# pentatonic.net
KiCad netlist of a schematic drawn in EAGLE
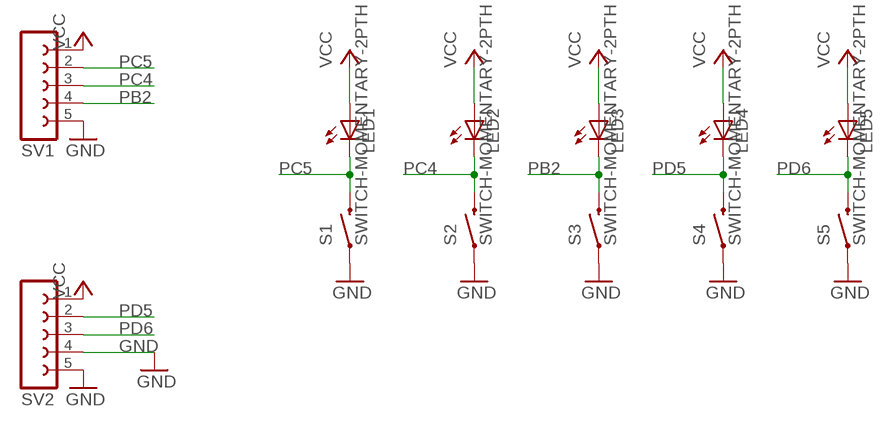
[diagram p0: schematic, sheet 1]

(export (version "E")
  (design (tool "Eeschema 10.0.6"))
  (components
    (comp (ref "LED1")
      (value "LED5MM")
      (footprint "eagle-import:LED5MM")
      (libsource (lib "eagle-import") (part "LED5MM"))
    )
    (comp (ref "LED2")
      (value "LED5MM")
      (footprint "eagle-import:LED5MM")
      (libsource (lib "eagle-import") (part "LED5MM"))
    )
    (comp (ref "LED3")
      (value "LED5MM")
      (footprint "eagle-import:LED5MM")
      (libsource (lib "eagle-import") (part "LED5MM"))
    )
    (comp (ref "LED4")
      (value "LED5MM")
      (footprint "eagle-import:LED5MM")
      (libsource (lib "eagle-import") (part "LED5MM"))
    )
    (comp (ref "LED5")
      (value "LED5MM")
      (footprint "eagle-import:LED5MM")
      (libsource (lib "eagle-import") (part "LED5MM"))
    )
    (comp (ref "S1")
      (value "SWITCH-MOMENTARY-2PTH")
      (footprint "eagle-import:TACTILE-PTH")
      (libsource (lib "eagle-import") (part "SWITCH-MOMENTARY-2PTH"))
    )
    (comp (ref "S2")
      (value "SWITCH-MOMENTARY-2PTH")
      (footprint "eagle-import:TACTILE-PTH")
      (libsource (lib "eagle-import") (part "SWITCH-MOMENTARY-2PTH"))
    )
    (comp (ref "S3")
      (value "SWITCH-MOMENTARY-2PTH")
      (footprint "eagle-import:TACTILE-PTH")
      (libsource (lib "eagle-import") (part "SWITCH-MOMENTARY-2PTH"))
    )
    (comp (ref "S4")
      (value "SWITCH-MOMENTARY-2PTH")
      (footprint "eagle-import:TACTILE-PTH")
      (libsource (lib "eagle-import") (part "SWITCH-MOMENTARY-2PTH"))
    )
    (comp (ref "S5")
      (value "SWITCH-MOMENTARY-2PTH")
      (footprint "eagle-import:TACTILE-PTH")
      (libsource (lib "eagle-import") (part "SWITCH-MOMENTARY-2PTH"))
    )
    (comp (ref "SV1")
      (value "FE05-1")
      (footprint "eagle-import:FE05-1")
      (libsource (lib "eagle-import") (part "FE05-1"))
    )
    (comp (ref "SV2")
      (value "FE05-1")
      (footprint "eagle-import:FE05-1")
      (libsource (lib "eagle-import") (part "FE05-1"))
    )
  )
  (nets
    (net (code "1") (name "/PB2") (class "Default")
      (node (ref "LED3") (pin "K") (pinfunction "C_K") (pintype "passive"))
      (node (ref "S3") (pin "3") (pinfunction "2_3") (pintype "passive"))
      (node (ref "SV1") (pin "4") (pinfunction "4_4") (pintype "passive"))
    )
    (net (code "2") (name "/PC4") (class "Default")
      (node (ref "LED2") (pin "K") (pinfunction "C_K") (pintype "passive"))
      (node (ref "S2") (pin "3") (pinfunction "2_3") (pintype "passive"))
      (node (ref "SV1") (pin "3") (pinfunction "3_3") (pintype "passive"))
    )
    (net (code "3") (name "/PC5") (class "Default")
      (node (ref "LED1") (pin "K") (pinfunction "C_K") (pintype "passive"))
      (node (ref "S1") (pin "3") (pinfunction "2_3") (pintype "passive"))
      (node (ref "SV1") (pin "2") (pinfunction "2_2") (pintype "passive"))
    )
    (net (code "4") (name "/PD5") (class "Default")
      (node (ref "LED4") (pin "K") (pinfunction "C_K") (pintype "passive"))
      (node (ref "S4") (pin "3") (pinfunction "2_3") (pintype "passive"))
      (node (ref "SV2") (pin "2") (pinfunction "2_2") (pintype "passive"))
    )
    (net (code "5") (name "/PD6") (class "Default")
      (node (ref "LED5") (pin "K") (pinfunction "C_K") (pintype "passive"))
      (node (ref "S5") (pin "3") (pinfunction "2_3") (pintype "passive"))
      (node (ref "SV2") (pin "3") (pinfunction "3_3") (pintype "passive"))
    )
    (net (code "6") (name "GND") (class "Default")
      (node (ref "S1") (pin "1") (pinfunction "1_1") (pintype "passive"))
      (node (ref "S2") (pin "1") (pinfunction "1_1") (pintype "passive"))
      (node (ref "S3") (pin "1") (pinfunction "1_1") (pintype "passive"))
      (node (ref "S4") (pin "1") (pinfunction "1_1") (pintype "passive"))
      (node (ref "S5") (pin "1") (pinfunction "1_1") (pintype "passive"))
      (node (ref "SV1") (pin "5") (pinfunction "5_5") (pintype "passive"))
      (node (ref "SV2") (pin "4") (pinfunction "4_4") (pintype "passive"))
      (node (ref "SV2") (pin "5") (pinfunction "5_5") (pintype "passive"))
    )
    (net (code "7") (name "VCC") (class "Default")
      (node (ref "LED1") (pin "A") (pinfunction "A_A") (pintype "passive"))
      (node (ref "LED2") (pin "A") (pinfunction "A_A") (pintype "passive"))
      (node (ref "LED3") (pin "A") (pinfunction "A_A") (pintype "passive"))
      (node (ref "LED4") (pin "A") (pinfunction "A_A") (pintype "passive"))
      (node (ref "LED5") (pin "A") (pinfunction "A_A") (pintype "passive"))
      (node (ref "SV1") (pin "1") (pinfunction "1_1") (pintype "passive"))
      (node (ref "SV2") (pin "1") (pinfunction "1_1") (pintype "passive"))
    )
  )
)
